# Signals.net
KiCad netlist of a schematic drawn in Altium Designer
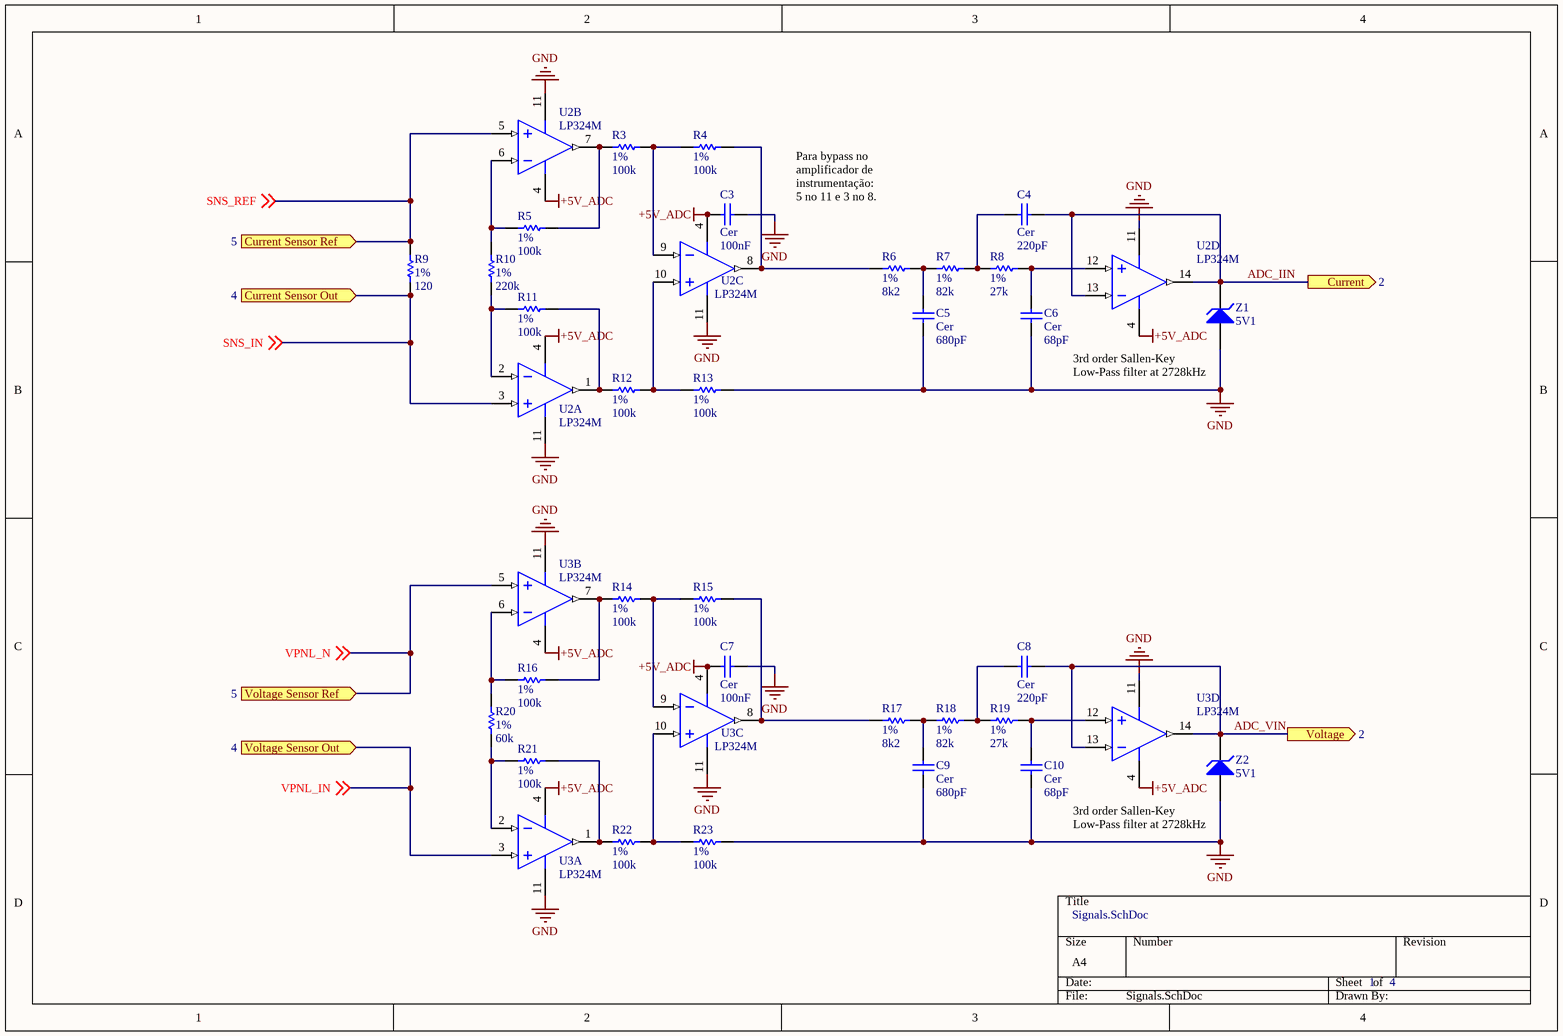
[diagram p0: Signals.SchDoc]

(export (version "E")
  (design (tool "Eeschema 10.0.6"))
  (components
    (comp (ref "C3")
      (value "Cer")
      (footprint "C1210_M")
      (description "Capacitor")
      (fields (field (name "ALTIUM_VALUE") "100nF") (field (name "PUBLISHER") "Altium Limited"))
      (libsource (lib "Miscellaneous Devices") (part "Cap"))
    )
    (comp (ref "C4")
      (value "Cer")
      (footprint "PCB1_corrosao:6-0805_M")
      (description "Capacitor")
      (fields (field (name "ALTIUM_VALUE") "220pF") (field (name "PUBLISHER") "Altium Limited"))
      (libsource (lib "Miscellaneous Devices") (part "Cap"))
    )
    (comp (ref "C5")
      (value "Cer")
      (footprint "PCB1_corrosao:6-0805_M")
      (description "Capacitor")
      (fields (field (name "ALTIUM_VALUE") "680pF") (field (name "PUBLISHER") "Altium Limited"))
      (libsource (lib "Miscellaneous Devices") (part "Cap"))
    )
    (comp (ref "C6")
      (value "Cer")
      (footprint "PCB1_corrosao:6-0805_M")
      (description "Capacitor")
      (fields (field (name "ALTIUM_VALUE") "68pF") (field (name "PUBLISHER") "Altium Limited"))
      (libsource (lib "Miscellaneous Devices") (part "Cap"))
    )
    (comp (ref "C7")
      (value "Cer")
      (footprint "C1210_M")
      (description "Capacitor")
      (fields (field (name "ALTIUM_VALUE") "100nF") (field (name "PUBLISHER") "Altium Limited"))
      (libsource (lib "Miscellaneous Devices") (part "Cap"))
    )
    (comp (ref "C8")
      (value "Cer")
      (footprint "PCB1_corrosao:6-0805_M")
      (description "Capacitor")
      (fields (field (name "ALTIUM_VALUE") "220pF") (field (name "PUBLISHER") "Altium Limited"))
      (libsource (lib "Miscellaneous Devices") (part "Cap"))
    )
    (comp (ref "C9")
      (value "Cer")
      (footprint "PCB1_corrosao:6-0805_M")
      (description "Capacitor")
      (fields (field (name "ALTIUM_VALUE") "680pF") (field (name "PUBLISHER") "Altium Limited"))
      (libsource (lib "Miscellaneous Devices") (part "Cap"))
    )
    (comp (ref "C10")
      (value "Cer")
      (footprint "PCB1_corrosao:6-0805_M")
      (description "Capacitor")
      (fields (field (name "ALTIUM_VALUE") "68pF") (field (name "PUBLISHER") "Altium Limited"))
      (libsource (lib "Miscellaneous Devices") (part "Cap"))
    )
    (comp (ref "R3")
      (value "1%")
      (footprint "6-0805_M")
      (description "Resistor")
      (fields (field (name "ALTIUM_VALUE") "100k") (field (name "PUBLISHER") "Altium Limited"))
      (libsource (lib "Miscellaneous Devices") (part "Res1"))
    )
    (comp (ref "R4")
      (value "1%")
      (footprint "6-0805_M")
      (description "Resistor")
      (fields (field (name "ALTIUM_VALUE") "100k") (field (name "PUBLISHER") "Altium Limited"))
      (libsource (lib "Miscellaneous Devices") (part "Res1"))
    )
    (comp (ref "R5")
      (value "1%")
      (footprint "6-0805_M")
      (description "Resistor")
      (fields (field (name "ALTIUM_VALUE") "100k") (field (name "PUBLISHER") "Altium Limited"))
      (libsource (lib "Miscellaneous Devices") (part "Res1"))
    )
    (comp (ref "R6")
      (value "1%")
      (footprint "6-0805_M")
      (description "Resistor")
      (fields (field (name "ALTIUM_VALUE") "8k2") (field (name "PUBLISHER") "Altium Limited"))
      (libsource (lib "Miscellaneous Devices") (part "Res1"))
    )
    (comp (ref "R7")
      (value "1%")
      (footprint "6-0805_M")
      (description "Resistor")
      (fields (field (name "ALTIUM_VALUE") "82k") (field (name "PUBLISHER") "Altium Limited"))
      (libsource (lib "Miscellaneous Devices") (part "Res1"))
    )
    (comp (ref "R8")
      (value "1%")
      (footprint "6-0805_M")
      (description "Resistor")
      (fields (field (name "ALTIUM_VALUE") "27k") (field (name "PUBLISHER") "Altium Limited"))
      (libsource (lib "Miscellaneous Devices") (part "Res1"))
    )
    (comp (ref "R9")
      (value "1%")
      (footprint "6-0805_M")
      (description "Resistor")
      (fields (field (name "ALTIUM_VALUE") "120") (field (name "PUBLISHER") "Altium Limited"))
      (libsource (lib "Miscellaneous Devices") (part "Res1"))
    )
    (comp (ref "R10")
      (value "1%")
      (footprint "6-0805_M")
      (description "Resistor")
      (fields (field (name "ALTIUM_VALUE") "220k") (field (name "PUBLISHER") "Altium Limited"))
      (libsource (lib "Miscellaneous Devices") (part "Res1"))
    )
    (comp (ref "R11")
      (value "1%")
      (footprint "6-0805_M")
      (description "Resistor")
      (fields (field (name "ALTIUM_VALUE") "100k") (field (name "PUBLISHER") "Altium Limited"))
      (libsource (lib "Miscellaneous Devices") (part "Res1"))
    )
    (comp (ref "R12")
      (value "1%")
      (footprint "6-0805_M")
      (description "Resistor")
      (fields (field (name "ALTIUM_VALUE") "100k") (field (name "PUBLISHER") "Altium Limited"))
      (libsource (lib "Miscellaneous Devices") (part "Res1"))
    )
    (comp (ref "R13")
      (value "1%")
      (footprint "6-0805_M")
      (description "Resistor")
      (fields (field (name "ALTIUM_VALUE") "100k") (field (name "PUBLISHER") "Altium Limited"))
      (libsource (lib "Miscellaneous Devices") (part "Res1"))
    )
    (comp (ref "R14")
      (value "1%")
      (footprint "6-0805_M")
      (description "Resistor")
      (fields (field (name "ALTIUM_VALUE") "100k") (field (name "PUBLISHER") "Altium Limited"))
      (libsource (lib "Miscellaneous Devices") (part "Res1"))
    )
    (comp (ref "R15")
      (value "1%")
      (footprint "6-0805_M")
      (description "Resistor")
      (fields (field (name "ALTIUM_VALUE") "100k") (field (name "PUBLISHER") "Altium Limited"))
      (libsource (lib "Miscellaneous Devices") (part "Res1"))
    )
    (comp (ref "R16")
      (value "1%")
      (footprint "6-0805_M")
      (description "Resistor")
      (fields (field (name "ALTIUM_VALUE") "100k") (field (name "PUBLISHER") "Altium Limited"))
      (libsource (lib "Miscellaneous Devices") (part "Res1"))
    )
    (comp (ref "R17")
      (value "1%")
      (footprint "6-0805_M")
      (description "Resistor")
      (fields (field (name "ALTIUM_VALUE") "8k2") (field (name "PUBLISHER") "Altium Limited"))
      (libsource (lib "Miscellaneous Devices") (part "Res1"))
    )
    (comp (ref "R18")
      (value "1%")
      (footprint "6-0805_M")
      (description "Resistor")
      (fields (field (name "ALTIUM_VALUE") "82k") (field (name "PUBLISHER") "Altium Limited"))
      (libsource (lib "Miscellaneous Devices") (part "Res1"))
    )
    (comp (ref "R19")
      (value "1%")
      (footprint "6-0805_M")
      (description "Resistor")
      (fields (field (name "ALTIUM_VALUE") "27k") (field (name "PUBLISHER") "Altium Limited"))
      (libsource (lib "Miscellaneous Devices") (part "Res1"))
    )
    (comp (ref "R20")
      (value "1%")
      (footprint "6-0805_M")
      (description "Resistor")
      (fields (field (name "ALTIUM_VALUE") "60k") (field (name "PUBLISHER") "Altium Limited"))
      (libsource (lib "Miscellaneous Devices") (part "Res1"))
    )
    (comp (ref "R21")
      (value "1%")
      (footprint "6-0805_M")
      (description "Resistor")
      (fields (field (name "ALTIUM_VALUE") "100k") (field (name "PUBLISHER") "Altium Limited"))
      (libsource (lib "Miscellaneous Devices") (part "Res1"))
    )
    (comp (ref "R22")
      (value "1%")
      (footprint "6-0805_M")
      (description "Resistor")
      (fields (field (name "ALTIUM_VALUE") "100k") (field (name "PUBLISHER") "Altium Limited"))
      (libsource (lib "Miscellaneous Devices") (part "Res1"))
    )
    (comp (ref "R23")
      (value "1%")
      (footprint "6-0805_M")
      (description "Resistor")
      (fields (field (name "ALTIUM_VALUE") "100k") (field (name "PUBLISHER") "Altium Limited"))
      (libsource (lib "Miscellaneous Devices") (part "Res1"))
    )
    (comp (ref "U2")
      (value "LP324M")
      (footprint "M14A_M")
      (description "Micropower Quad Operational Amplifier")
      (fields
        (field (name "MANUFACTURER") "National Semiconductor")
        (field (name "DIGIKEYPARTNUMBER") "LP324MXCT-ND")
        (field (name "PUBLISHER") "Altium Limited")
      )
      (libsource (lib "NSC Amplifier") (part "LP324M"))
    )
    (comp (ref "U3")
      (value "LP324M")
      (footprint "M14A_M")
      (description "Micropower Quad Operational Amplifier")
      (fields
        (field (name "MANUFACTURER") "National Semiconductor")
        (field (name "DIGIKEYPARTNUMBER") "LP324MXCT-ND")
        (field (name "PUBLISHER") "Altium Limited")
      )
      (libsource (lib "NSC Amplifier") (part "LP324M"))
    )
    (comp (ref "Z1")
      (value "5V1")
      (footprint "PCB1_corrosao:C1210_M")
      (description "Zener Diode")
      (fields (field (name "PUBLISHER") "Altium Limited"))
      (libsource (lib "Miscellaneous Devices") (part "D Zener"))
    )
    (comp (ref "Z2")
      (value "5V1")
      (footprint "PCB1_corrosao:C1210_M")
      (description "Zener Diode")
      (fields (field (name "PUBLISHER") "Altium Limited"))
      (libsource (lib "Miscellaneous Devices") (part "D Zener"))
    )
  )
  (nets
    (net (code "1") (name "+5V_ADC") (class "Default")
      (node (ref "C3") (pin "2") (pinfunction "2_2") (pintype "passive"))
      (node (ref "C7") (pin "2") (pinfunction "2_2") (pintype "passive"))
      (node (ref "U2") (pin "4") (pinfunction "V+_4") (pintype "power_in"))
      (node (ref "U3") (pin "4") (pinfunction "V+_4") (pintype "power_in"))
    )
    (net (code "2") (name "/ADC_IIN") (class "Default")
      (node (ref "C4") (pin "2") (pinfunction "2_2") (pintype "passive"))
      (node (ref "U2") (pin "13") (pinfunction "IN4-_13") (pintype "input"))
      (node (ref "U2") (pin "14") (pinfunction "OUT4_14") (pintype "output"))
      (node (ref "Z1") (pin "2") (pinfunction "K_2") (pintype "passive"))
    )
    (net (code "3") (name "/ADC_VIN") (class "Default")
      (node (ref "C8") (pin "2") (pinfunction "2_2") (pintype "passive"))
      (node (ref "U3") (pin "13") (pinfunction "IN4-_13") (pintype "input"))
      (node (ref "U3") (pin "14") (pinfunction "OUT4_14") (pintype "output"))
      (node (ref "Z2") (pin "2") (pinfunction "K_2") (pintype "passive"))
    )
    (net (code "4") (name "GND") (class "Default")
      (node (ref "C10") (pin "1") (pinfunction "1_1") (pintype "passive"))
      (node (ref "C3") (pin "1") (pinfunction "1_1") (pintype "passive"))
      (node (ref "C5") (pin "1") (pinfunction "1_1") (pintype "passive"))
      (node (ref "C6") (pin "1") (pinfunction "1_1") (pintype "passive"))
      (node (ref "C7") (pin "1") (pinfunction "1_1") (pintype "passive"))
      (node (ref "C9") (pin "1") (pinfunction "1_1") (pintype "passive"))
      (node (ref "R13") (pin "1") (pinfunction "1_1") (pintype "passive"))
      (node (ref "R23") (pin "1") (pinfunction "1_1") (pintype "passive"))
      (node (ref "U2") (pin "11") (pinfunction "GND_11") (pintype "power_in"))
      (node (ref "U3") (pin "11") (pinfunction "GND_11") (pintype "power_in"))
      (node (ref "Z1") (pin "1") (pinfunction "A_1") (pintype "passive"))
      (node (ref "Z2") (pin "1") (pinfunction "A_1") (pintype "passive"))
    )
    (net (code "5") (name "Net-(C4-Pad1)") (class "Default")
      (node (ref "C4") (pin "1") (pinfunction "1_1") (pintype "passive"))
      (node (ref "R7") (pin "1") (pinfunction "1_1") (pintype "passive"))
      (node (ref "R8") (pin "2") (pinfunction "2_2") (pintype "passive"))
    )
    (net (code "6") (name "Net-(C5-Pad2)") (class "Default")
      (node (ref "C5") (pin "2") (pinfunction "2_2") (pintype "passive"))
      (node (ref "R6") (pin "1") (pinfunction "1_1") (pintype "passive"))
      (node (ref "R7") (pin "2") (pinfunction "2_2") (pintype "passive"))
    )
    (net (code "7") (name "Net-(C8-Pad1)") (class "Default")
      (node (ref "C8") (pin "1") (pinfunction "1_1") (pintype "passive"))
      (node (ref "R18") (pin "1") (pinfunction "1_1") (pintype "passive"))
      (node (ref "R19") (pin "2") (pinfunction "2_2") (pintype "passive"))
    )
    (net (code "8") (name "Net-(C9-Pad2)") (class "Default")
      (node (ref "C9") (pin "2") (pinfunction "2_2") (pintype "passive"))
      (node (ref "R17") (pin "1") (pinfunction "1_1") (pintype "passive"))
      (node (ref "R18") (pin "2") (pinfunction "2_2") (pintype "passive"))
    )
    (net (code "9") (name "Net-(U2A-IN1-)") (class "Default")
      (node (ref "R10") (pin "1") (pinfunction "1_1") (pintype "passive"))
      (node (ref "R11") (pin "2") (pinfunction "2_2") (pintype "passive"))
      (node (ref "U2") (pin "2") (pinfunction "IN1-_2") (pintype "input"))
    )
    (net (code "10") (name "Net-(U2A-OUT1)") (class "Default")
      (node (ref "R11") (pin "1") (pinfunction "1_1") (pintype "passive"))
      (node (ref "R12") (pin "2") (pinfunction "2_2") (pintype "passive"))
      (node (ref "U2") (pin "1") (pinfunction "OUT1_1") (pintype "output"))
    )
    (net (code "11") (name "Net-(U2B-IN2-)") (class "Default")
      (node (ref "R10") (pin "2") (pinfunction "2_2") (pintype "passive"))
      (node (ref "R5") (pin "1") (pinfunction "1_1") (pintype "passive"))
      (node (ref "U2") (pin "6") (pinfunction "IN2-_6") (pintype "input"))
    )
    (net (code "12") (name "Net-(U2B-OUT2)") (class "Default")
      (node (ref "R3") (pin "2") (pinfunction "2_2") (pintype "passive"))
      (node (ref "R5") (pin "2") (pinfunction "2_2") (pintype "passive"))
      (node (ref "U2") (pin "7") (pinfunction "OUT2_7") (pintype "output"))
    )
    (net (code "13") (name "Net-(U2C-IN3+)") (class "Default")
      (node (ref "R12") (pin "1") (pinfunction "1_1") (pintype "passive"))
      (node (ref "R13") (pin "2") (pinfunction "2_2") (pintype "passive"))
      (node (ref "U2") (pin "10") (pinfunction "IN3+_10") (pintype "input"))
    )
    (net (code "14") (name "Net-(U2C-IN3-)") (class "Default")
      (node (ref "R3") (pin "1") (pinfunction "1_1") (pintype "passive"))
      (node (ref "R4") (pin "2") (pinfunction "2_2") (pintype "passive"))
      (node (ref "U2") (pin "9") (pinfunction "IN3-_9") (pintype "input"))
    )
    (net (code "15") (name "Net-(U2C-OUT3)") (class "Default")
      (node (ref "R4") (pin "1") (pinfunction "1_1") (pintype "passive"))
      (node (ref "R6") (pin "2") (pinfunction "2_2") (pintype "passive"))
      (node (ref "U2") (pin "8") (pinfunction "OUT3_8") (pintype "output"))
    )
    (net (code "16") (name "Net-(U2D-IN4+)") (class "Default")
      (node (ref "C6") (pin "2") (pinfunction "2_2") (pintype "passive"))
      (node (ref "R8") (pin "1") (pinfunction "1_1") (pintype "passive"))
      (node (ref "U2") (pin "12") (pinfunction "IN4+_12") (pintype "input"))
    )
    (net (code "17") (name "Net-(U3A-IN1-)") (class "Default")
      (node (ref "R20") (pin "1") (pinfunction "1_1") (pintype "passive"))
      (node (ref "R21") (pin "2") (pinfunction "2_2") (pintype "passive"))
      (node (ref "U3") (pin "2") (pinfunction "IN1-_2") (pintype "input"))
    )
    (net (code "18") (name "Net-(U3A-OUT1)") (class "Default")
      (node (ref "R21") (pin "1") (pinfunction "1_1") (pintype "passive"))
      (node (ref "R22") (pin "2") (pinfunction "2_2") (pintype "passive"))
      (node (ref "U3") (pin "1") (pinfunction "OUT1_1") (pintype "output"))
    )
    (net (code "19") (name "Net-(U3B-IN2-)") (class "Default")
      (node (ref "R16") (pin "1") (pinfunction "1_1") (pintype "passive"))
      (node (ref "R20") (pin "2") (pinfunction "2_2") (pintype "passive"))
      (node (ref "U3") (pin "6") (pinfunction "IN2-_6") (pintype "input"))
    )
    (net (code "20") (name "Net-(U3B-OUT2)") (class "Default")
      (node (ref "R14") (pin "2") (pinfunction "2_2") (pintype "passive"))
      (node (ref "R16") (pin "2") (pinfunction "2_2") (pintype "passive"))
      (node (ref "U3") (pin "7") (pinfunction "OUT2_7") (pintype "output"))
    )
    (net (code "21") (name "Net-(U3C-IN3+)") (class "Default")
      (node (ref "R22") (pin "1") (pinfunction "1_1") (pintype "passive"))
      (node (ref "R23") (pin "2") (pinfunction "2_2") (pintype "passive"))
      (node (ref "U3") (pin "10") (pinfunction "IN3+_10") (pintype "input"))
    )
    (net (code "22") (name "Net-(U3C-IN3-)") (class "Default")
      (node (ref "R14") (pin "1") (pinfunction "1_1") (pintype "passive"))
      (node (ref "R15") (pin "2") (pinfunction "2_2") (pintype "passive"))
      (node (ref "U3") (pin "9") (pinfunction "IN3-_9") (pintype "input"))
    )
    (net (code "23") (name "Net-(U3C-OUT3)") (class "Default")
      (node (ref "R15") (pin "1") (pinfunction "1_1") (pintype "passive"))
      (node (ref "R17") (pin "2") (pinfunction "2_2") (pintype "passive"))
      (node (ref "U3") (pin "8") (pinfunction "OUT3_8") (pintype "output"))
    )
    (net (code "24") (name "Net-(U3D-IN4+)") (class "Default")
      (node (ref "C10") (pin "2") (pinfunction "2_2") (pintype "passive"))
      (node (ref "R19") (pin "1") (pinfunction "1_1") (pintype "passive"))
      (node (ref "U3") (pin "12") (pinfunction "IN4+_12") (pintype "input"))
    )
    (net (code "25") (name "SNS_IN") (class "Default")
      (node (ref "R9") (pin "1") (pinfunction "1_1") (pintype "passive"))
      (node (ref "U2") (pin "3") (pinfunction "IN1+_3") (pintype "input"))
    )
    (net (code "26") (name "SNS_REF") (class "Default")
      (node (ref "R9") (pin "2") (pinfunction "2_2") (pintype "passive"))
      (node (ref "U2") (pin "5") (pinfunction "IN2+_5") (pintype "input"))
    )
    (net (code "27") (name "VPNL_IN") (class "Default")
      (node (ref "U3") (pin "3") (pinfunction "IN1+_3") (pintype "input"))
    )
    (net (code "28") (name "VPNL_N") (class "Default")
      (node (ref "U3") (pin "5") (pinfunction "IN2+_5") (pintype "input"))
    )
  )
)
